# 51MCU.net
KiCad netlist of a schematic drawn in Altium Designer
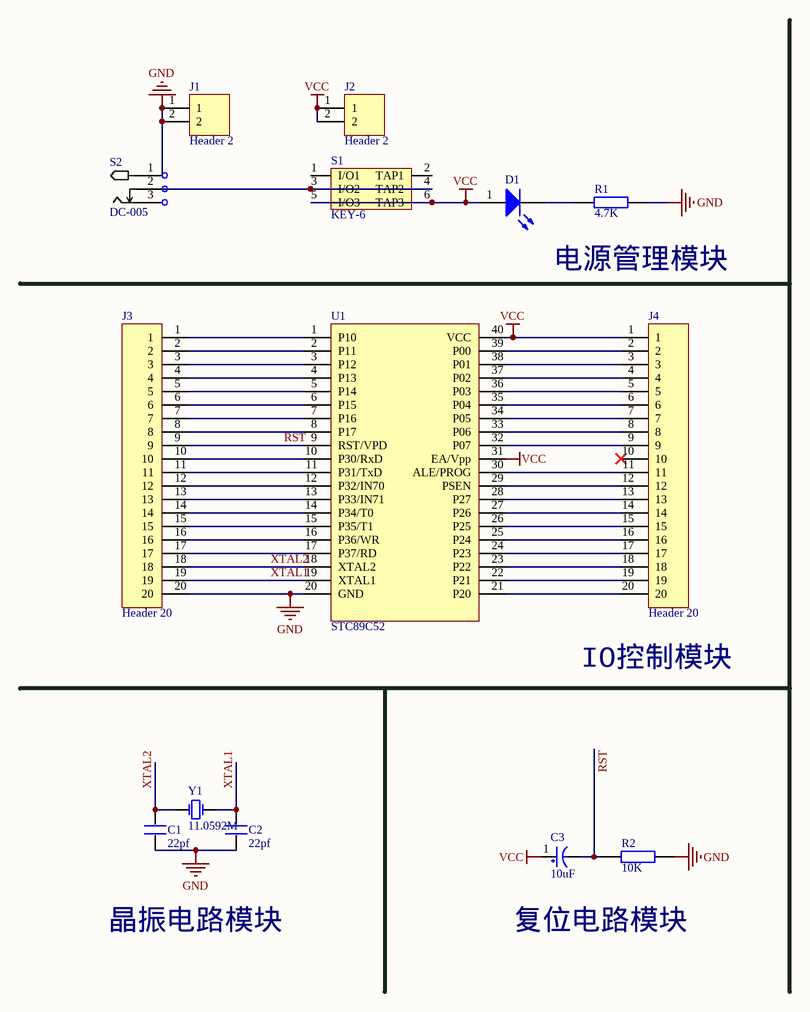
[diagram p0: 51MCU最小系统.SchDoc]

(export (version "E")
  (design (tool "Eeschema 10.0.6"))
  (components
    (comp (ref "C1")
      (value "22pf")
      (footprint "MyPcbLib:CAP_2.54_NO_ele")
      (libsource (lib "MySchLib") (part "C-dip"))
    )
    (comp (ref "C2")
      (value "22pf")
      (footprint "MyPcbLib:CAP_2.54_NO_ele")
      (libsource (lib "MySchLib") (part "C-dip"))
    )
    (comp (ref "C3")
      (value "10uF")
      (footprint "MyPcbLib:Cap_3.0")
      (libsource (lib "MySchLib") (part "C-ele"))
    )
    (comp (ref "D1")
      (value "LED-Diode-DIP")
      (footprint "MyPcbLib:LED_DIP")
      (libsource (lib "MySchLib") (part "LED-Diode-DIP"))
    )
    (comp (ref "J1")
      (value "Header 2")
      (footprint "MyPcbLib:Header 2")
      (libsource (lib "MySchLib") (part "Header 2"))
    )
    (comp (ref "J2")
      (value "Header 2")
      (footprint "MyPcbLib:Header 2")
      (libsource (lib "MySchLib") (part "Header 2"))
    )
    (comp (ref "J3")
      (value "Header 20")
      (footprint "MyPcbLib:Header 20")
      (libsource (lib "MySchLib") (part "Header 20"))
    )
    (comp (ref "J4")
      (value "Header 20")
      (footprint "MyPcbLib:Header 20")
      (libsource (lib "") (part "Header 20_1"))
    )
    (comp (ref "R1")
      (value "4.7K")
      (footprint "MyPcbLib:Res-dip - duplicate")
      (libsource (lib "MySchLib") (part "Res-DIP"))
    )
    (comp (ref "R2")
      (value "10K")
      (footprint "MyPcbLib:Res-dip - duplicate")
      (libsource (lib "") (part "Res-DIP_1"))
    )
    (comp (ref "S1") (value "KEY-6") (footprint "MyPcbLib:Key-6") (libsource (lib "MySchLib") (part "KEY-6")))
    (comp (ref "S2")
      (value "DC-005")
      (footprint "MyPcbLib:DC-005")
      (libsource (lib "MySchLib") (part "DC-005"))
    )
    (comp (ref "U1")
      (value "STC89C52")
      (footprint "MyPcbLib:DIP-40")
      (libsource (lib "MySchLib") (part "STC89C52"))
    )
    (comp (ref "Y1")
      (value "11.0592M")
      (footprint "MyPcbLib:XTAL_SOP")
      (libsource (lib "MySchLib") (part "XTAL"))
    )
  )
  (nets
    (net (code "1") (name "/RST") (class "Default")
      (node (ref "C3") (pin "2") (pinfunction "GND_2") (pintype "passive"))
      (node (ref "J3") (pin "9") (pinfunction "9_9") (pintype "passive"))
      (node (ref "R2") (pin "2") (pinfunction "2_2") (pintype "passive"))
      (node (ref "U1") (pin "9") (pinfunction "RST/VPD_9") (pintype "passive"))
    )
    (net (code "2") (name "/XTAL1") (class "Default")
      (node (ref "C2") (pin "1") (pintype "passive"))
      (node (ref "J3") (pin "19") (pinfunction "19_19") (pintype "passive"))
      (node (ref "U1") (pin "19") (pinfunction "XTAL1_19") (pintype "passive"))
      (node (ref "Y1") (pin "1") (pinfunction "OSC1_1") (pintype "passive"))
    )
    (net (code "3") (name "/XTAL2") (class "Default")
      (node (ref "C1") (pin "1") (pintype "passive"))
      (node (ref "J3") (pin "18") (pinfunction "18_18") (pintype "passive"))
      (node (ref "U1") (pin "18") (pinfunction "XTAL2_18") (pintype "passive"))
      (node (ref "Y1") (pin "2") (pinfunction "OSC2_2") (pintype "passive"))
    )
    (net (code "4") (name "GND") (class "Default")
      (node (ref "C1") (pin "2") (pintype "passive"))
      (node (ref "C2") (pin "2") (pintype "passive"))
      (node (ref "J1") (pin "1") (pinfunction "1_1") (pintype "passive"))
      (node (ref "J1") (pin "2") (pinfunction "2_2") (pintype "passive"))
      (node (ref "J3") (pin "20") (pinfunction "20_20") (pintype "passive"))
      (node (ref "R1") (pin "2") (pinfunction "2_2") (pintype "passive"))
      (node (ref "R2") (pin "1") (pinfunction "1_1") (pintype "passive"))
      (node (ref "S2") (pin "1") (pinfunction "1_1") (pintype "passive"))
      (node (ref "U1") (pin "20") (pinfunction "GND_20") (pintype "passive"))
    )
    (net (code "5") (name "Net-(D1-K)") (class "Default")
      (node (ref "D1") (pin "2") (pinfunction "K_2") (pintype "passive"))
      (node (ref "R1") (pin "1") (pinfunction "1_1") (pintype "passive"))
    )
    (net (code "6") (name "Net-(S1-I{slash}O2)") (class "Default")
      (node (ref "S1") (pin "3") (pinfunction "I/O2_3") (pintype "passive"))
      (node (ref "S1") (pin "4") (pinfunction "TAP2_4") (pintype "passive"))
      (node (ref "S2") (pin "2") (pinfunction "2_2") (pintype "passive"))
    )
    (net (code "7") (name "Net-(U1-ALE{slash}PROG)") (class "Default")
      (node (ref "J4") (pin "11") (pinfunction "11_11") (pintype "passive"))
      (node (ref "U1") (pin "30") (pinfunction "ALE/PROG_30") (pintype "passive"))
    )
    (net (code "8") (name "Net-(U1-P00)") (class "Default")
      (node (ref "J4") (pin "2") (pinfunction "2_2") (pintype "passive"))
      (node (ref "U1") (pin "39") (pinfunction "P00_39") (pintype "passive"))
    )
    (net (code "9") (name "Net-(U1-P01)") (class "Default")
      (node (ref "J4") (pin "3") (pinfunction "3_3") (pintype "passive"))
      (node (ref "U1") (pin "38") (pinfunction "P01_38") (pintype "passive"))
    )
    (net (code "10") (name "Net-(U1-P02)") (class "Default")
      (node (ref "J4") (pin "4") (pinfunction "4_4") (pintype "passive"))
      (node (ref "U1") (pin "37") (pinfunction "P02_37") (pintype "passive"))
    )
    (net (code "11") (name "Net-(U1-P03)") (class "Default")
      (node (ref "J4") (pin "5") (pinfunction "5_5") (pintype "passive"))
      (node (ref "U1") (pin "36") (pinfunction "P03_36") (pintype "passive"))
    )
    (net (code "12") (name "Net-(U1-P04)") (class "Default")
      (node (ref "J4") (pin "6") (pinfunction "6_6") (pintype "passive"))
      (node (ref "U1") (pin "35") (pinfunction "P04_35") (pintype "passive"))
    )
    (net (code "13") (name "Net-(U1-P05)") (class "Default")
      (node (ref "J4") (pin "7") (pinfunction "7_7") (pintype "passive"))
      (node (ref "U1") (pin "34") (pinfunction "P05_34") (pintype "passive"))
    )
    (net (code "14") (name "Net-(U1-P06)") (class "Default")
      (node (ref "J4") (pin "8") (pinfunction "8_8") (pintype "passive"))
      (node (ref "U1") (pin "33") (pinfunction "P06_33") (pintype "passive"))
    )
    (net (code "15") (name "Net-(U1-P07)") (class "Default")
      (node (ref "J4") (pin "9") (pinfunction "9_9") (pintype "passive"))
      (node (ref "U1") (pin "32") (pinfunction "P07_32") (pintype "passive"))
    )
    (net (code "16") (name "Net-(U1-P10)") (class "Default")
      (node (ref "J3") (pin "1") (pinfunction "1_1") (pintype "passive"))
      (node (ref "U1") (pin "1") (pinfunction "P10_1") (pintype "passive"))
    )
    (net (code "17") (name "Net-(U1-P11)") (class "Default")
      (node (ref "J3") (pin "2") (pinfunction "2_2") (pintype "passive"))
      (node (ref "U1") (pin "2") (pinfunction "P11_2") (pintype "passive"))
    )
    (net (code "18") (name "Net-(U1-P12)") (class "Default")
      (node (ref "J3") (pin "3") (pinfunction "3_3") (pintype "passive"))
      (node (ref "U1") (pin "3") (pinfunction "P12_3") (pintype "passive"))
    )
    (net (code "19") (name "Net-(U1-P13)") (class "Default")
      (node (ref "J3") (pin "4") (pinfunction "4_4") (pintype "passive"))
      (node (ref "U1") (pin "4") (pinfunction "P13_4") (pintype "passive"))
    )
    (net (code "20") (name "Net-(U1-P14)") (class "Default")
      (node (ref "J3") (pin "5") (pinfunction "5_5") (pintype "passive"))
      (node (ref "U1") (pin "5") (pinfunction "P14_5") (pintype "passive"))
    )
    (net (code "21") (name "Net-(U1-P15)") (class "Default")
      (node (ref "J3") (pin "6") (pinfunction "6_6") (pintype "passive"))
      (node (ref "U1") (pin "6") (pinfunction "P15_6") (pintype "passive"))
    )
    (net (code "22") (name "Net-(U1-P16)") (class "Default")
      (node (ref "J3") (pin "7") (pinfunction "7_7") (pintype "passive"))
      (node (ref "U1") (pin "7") (pinfunction "P16_7") (pintype "passive"))
    )
    (net (code "23") (name "Net-(U1-P17)") (class "Default")
      (node (ref "J3") (pin "8") (pinfunction "8_8") (pintype "passive"))
      (node (ref "U1") (pin "8") (pinfunction "P17_8") (pintype "passive"))
    )
    (net (code "24") (name "Net-(U1-P20)") (class "Default")
      (node (ref "J4") (pin "20") (pinfunction "20_20") (pintype "passive"))
      (node (ref "U1") (pin "21") (pinfunction "P20_21") (pintype "passive"))
    )
    (net (code "25") (name "Net-(U1-P21)") (class "Default")
      (node (ref "J4") (pin "19") (pinfunction "19_19") (pintype "passive"))
      (node (ref "U1") (pin "22") (pinfunction "P21_22") (pintype "passive"))
    )
    (net (code "26") (name "Net-(U1-P22)") (class "Default")
      (node (ref "J4") (pin "18") (pinfunction "18_18") (pintype "passive"))
      (node (ref "U1") (pin "23") (pinfunction "P22_23") (pintype "passive"))
    )
    (net (code "27") (name "Net-(U1-P23)") (class "Default")
      (node (ref "J4") (pin "17") (pinfunction "17_17") (pintype "passive"))
      (node (ref "U1") (pin "24") (pinfunction "P23_24") (pintype "passive"))
    )
    (net (code "28") (name "Net-(U1-P24)") (class "Default")
      (node (ref "J4") (pin "16") (pinfunction "16_16") (pintype "passive"))
      (node (ref "U1") (pin "25") (pinfunction "P24_25") (pintype "passive"))
    )
    (net (code "29") (name "Net-(U1-P25)") (class "Default")
      (node (ref "J4") (pin "15") (pinfunction "15_15") (pintype "passive"))
      (node (ref "U1") (pin "26") (pinfunction "P25_26") (pintype "passive"))
    )
    (net (code "30") (name "Net-(U1-P26)") (class "Default")
      (node (ref "J4") (pin "14") (pinfunction "14_14") (pintype "passive"))
      (node (ref "U1") (pin "27") (pinfunction "P26_27") (pintype "passive"))
    )
    (net (code "31") (name "Net-(U1-P27)") (class "Default")
      (node (ref "J4") (pin "13") (pinfunction "13_13") (pintype "passive"))
      (node (ref "U1") (pin "28") (pinfunction "P27_28") (pintype "passive"))
    )
    (net (code "32") (name "Net-(U1-P30{slash}RxD)") (class "Default")
      (node (ref "J3") (pin "10") (pinfunction "10_10") (pintype "passive"))
      (node (ref "U1") (pin "10") (pinfunction "P30/RxD_10") (pintype "passive"))
    )
    (net (code "33") (name "Net-(U1-P31{slash}TxD)") (class "Default")
      (node (ref "J3") (pin "11") (pinfunction "11_11") (pintype "passive"))
      (node (ref "U1") (pin "11") (pinfunction "P31/TxD_11") (pintype "passive"))
    )
    (net (code "34") (name "Net-(U1-P32{slash}IN70)") (class "Default")
      (node (ref "J3") (pin "12") (pinfunction "12_12") (pintype "passive"))
      (node (ref "U1") (pin "12") (pinfunction "P32/IN70_12") (pintype "passive"))
    )
    (net (code "35") (name "Net-(U1-P33{slash}IN71)") (class "Default")
      (node (ref "J3") (pin "13") (pinfunction "13_13") (pintype "passive"))
      (node (ref "U1") (pin "13") (pinfunction "P33/IN71_13") (pintype "passive"))
    )
    (net (code "36") (name "Net-(U1-P34{slash}T0)") (class "Default")
      (node (ref "J3") (pin "14") (pinfunction "14_14") (pintype "passive"))
      (node (ref "U1") (pin "14") (pinfunction "P34/T0_14") (pintype "passive"))
    )
    (net (code "37") (name "Net-(U1-P35{slash}T1)") (class "Default")
      (node (ref "J3") (pin "15") (pinfunction "15_15") (pintype "passive"))
      (node (ref "U1") (pin "15") (pinfunction "P35/T1_15") (pintype "passive"))
    )
    (net (code "38") (name "Net-(U1-P36{slash}WR)") (class "Default")
      (node (ref "J3") (pin "16") (pinfunction "16_16") (pintype "passive"))
      (node (ref "U1") (pin "16") (pinfunction "P36/WR_16") (pintype "passive"))
    )
    (net (code "39") (name "Net-(U1-P37{slash}RD)") (class "Default")
      (node (ref "J3") (pin "17") (pinfunction "17_17") (pintype "passive"))
      (node (ref "U1") (pin "17") (pinfunction "P37/RD_17") (pintype "passive"))
    )
    (net (code "40") (name "Net-(U1-PSEN)") (class "Default")
      (node (ref "J4") (pin "12") (pinfunction "12_12") (pintype "passive"))
      (node (ref "U1") (pin "29") (pinfunction "PSEN_29") (pintype "passive"))
    )
    (net (code "41") (name "VCC") (class "Default")
      (node (ref "C3") (pin "1") (pinfunction "VCC_1") (pintype "passive"))
      (node (ref "D1") (pin "1") (pinfunction "A_1") (pintype "passive"))
      (node (ref "J2") (pin "1") (pinfunction "1_1") (pintype "passive"))
      (node (ref "J2") (pin "2") (pinfunction "2_2") (pintype "passive"))
      (node (ref "J4") (pin "1") (pinfunction "1_1") (pintype "passive"))
      (node (ref "S1") (pin "5") (pinfunction "I/O3_5") (pintype "passive"))
      (node (ref "S1") (pin "6") (pinfunction "TAP3_6") (pintype "passive"))
      (node (ref "U1") (pin "31") (pinfunction "EA/Vpp_31") (pintype "passive"))
      (node (ref "U1") (pin "40") (pinfunction "VCC_40") (pintype "passive"))
    )
    (net (code "42") (name "unconnected-(J4-Pad10)") (class "Default")
      (node (ref "J4") (pin "10") (pinfunction "10_10") (pintype "passive+no_connect"))
    )
    (net (code "43") (name "unconnected-(S1-I{slash}O1-Pad1)") (class "Default")
      (node (ref "S1") (pin "1") (pinfunction "I/O1_1") (pintype "passive"))
    )
    (net (code "44") (name "unconnected-(S1-TAP1-Pad2)") (class "Default")
      (node (ref "S1") (pin "2") (pinfunction "TAP1_2") (pintype "passive"))
    )
    (net (code "45") (name "unconnected-(S2-Pad3)") (class "Default")
      (node (ref "S2") (pin "3") (pinfunction "3_3") (pintype "passive"))
    )
  )
)
